# f103ret6_w25q64_20210714.net
KiCad netlist of a schematic drawn in Altium Designer
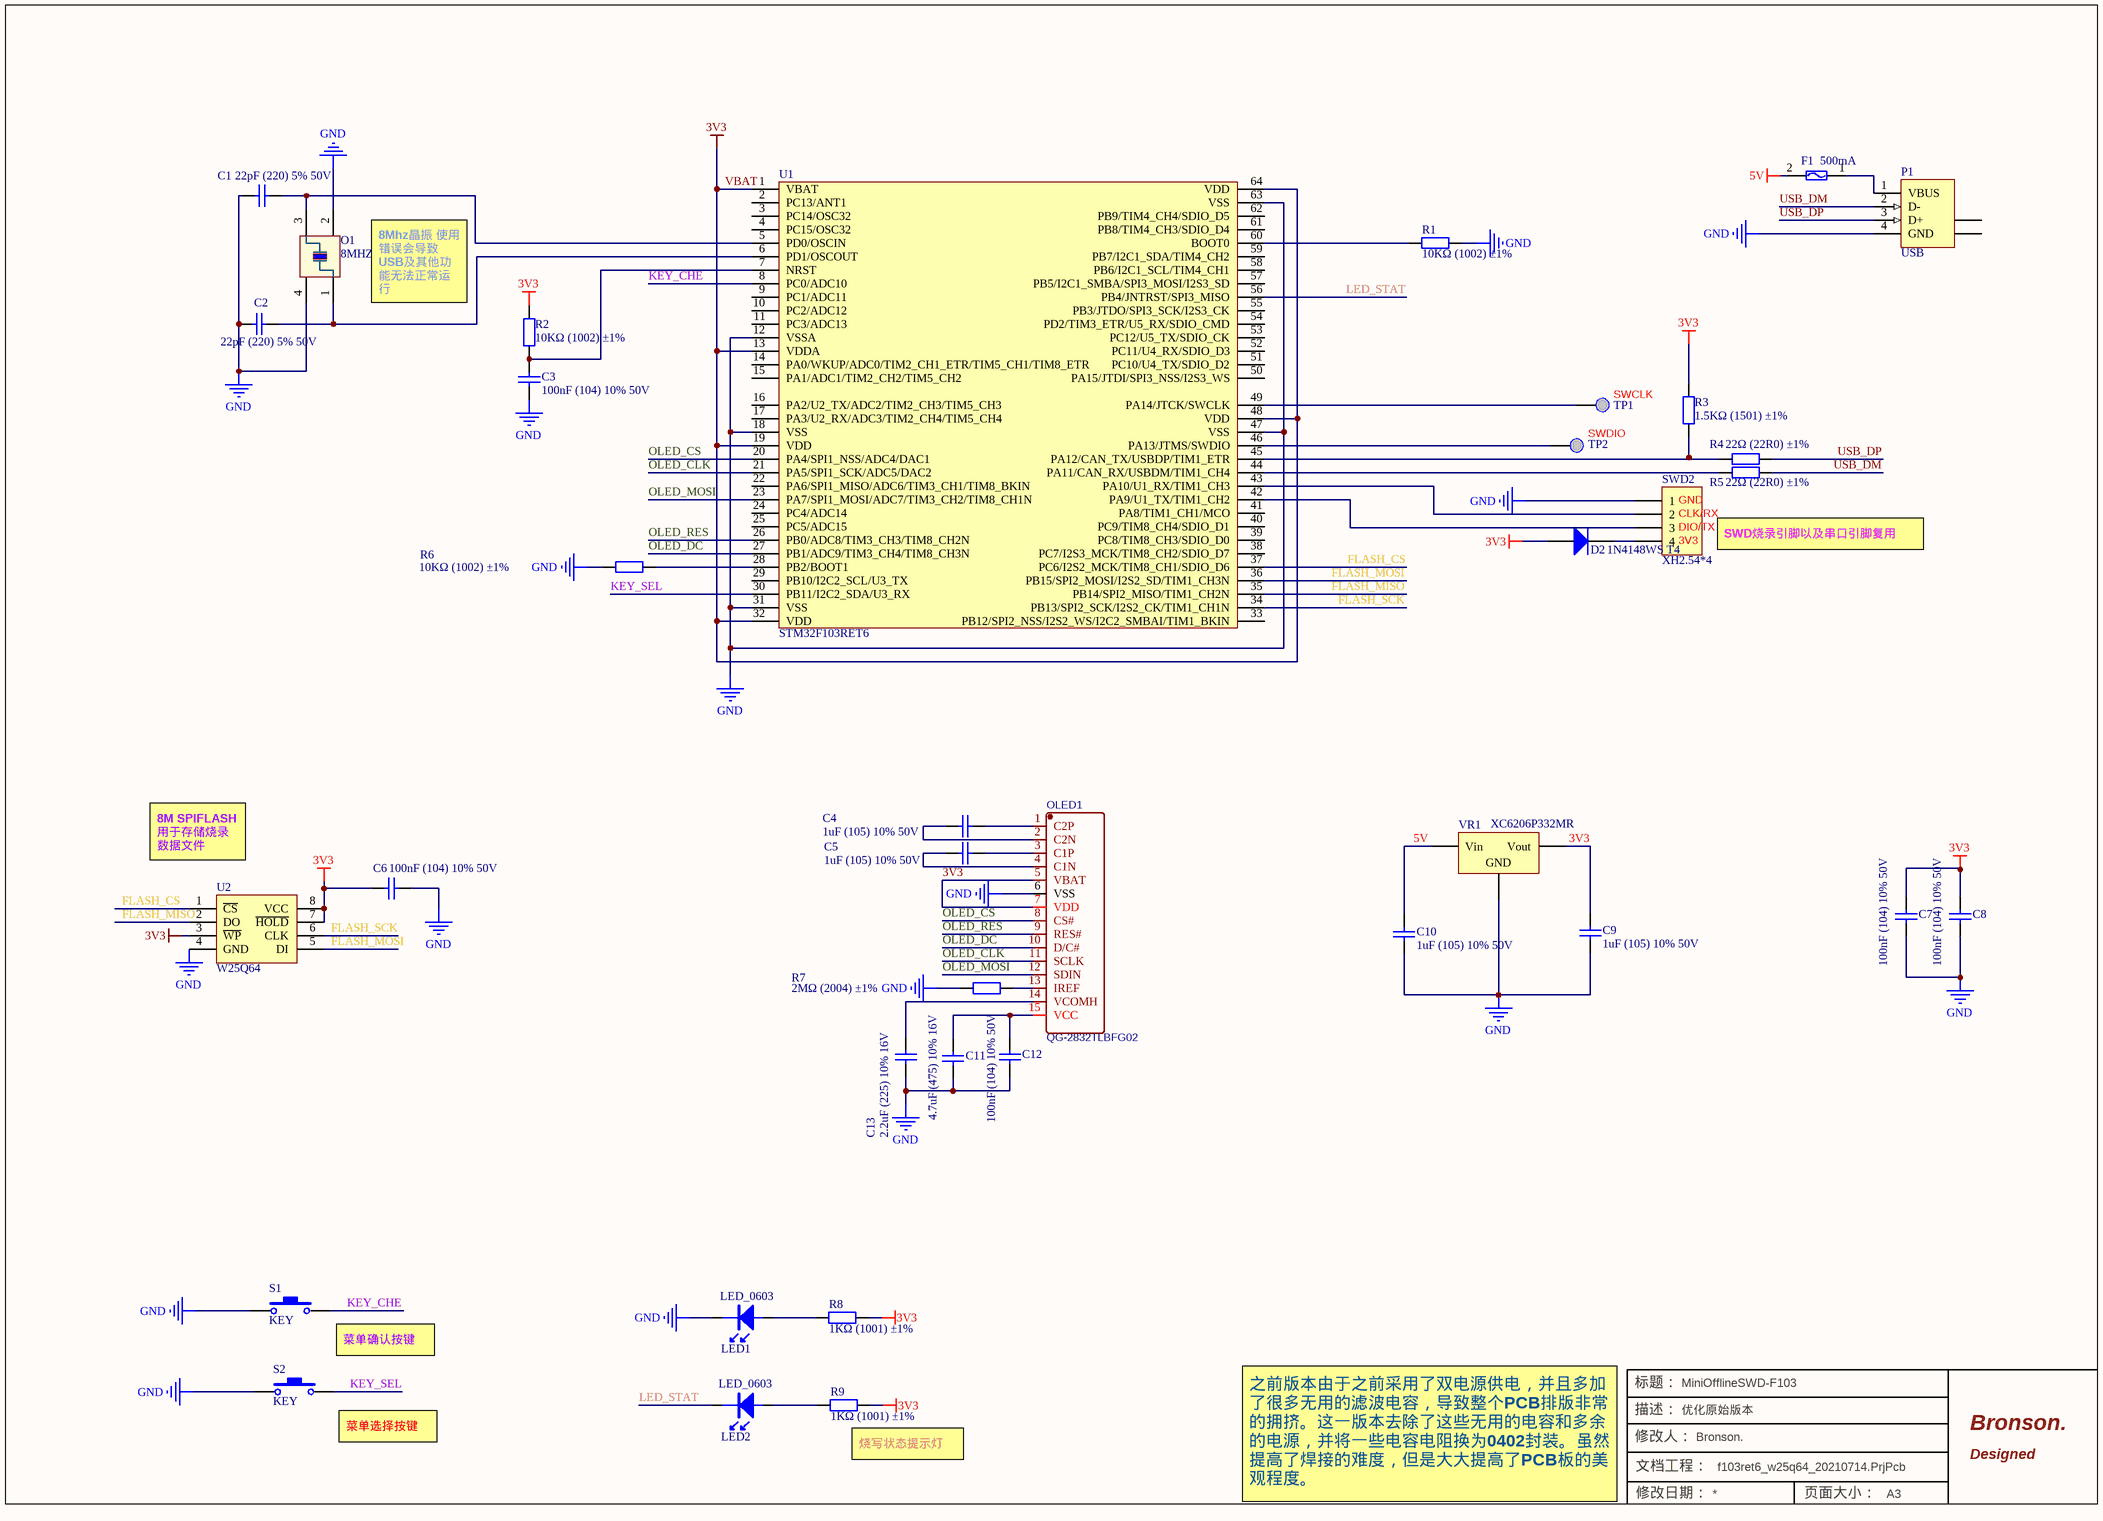
[diagram p0: f103ret6_w25q64_20210714.SchDoc]

(export (version "E")
  (design (tool "Eeschema 10.0.6"))
  (components
    (comp (ref "C1")
      (value "22pF (220) 5% 50V")
      (footprint "C0402")
      (description "贴片电容")
      (libsource (lib "Miscellaneous Devices LC") (part "0603 22pF (220) 5% 50V"))
    )
    (comp (ref "C2")
      (value "22pF (220) 5% 50V")
      (footprint "C0402")
      (description "贴片电容")
      (libsource (lib "Miscellaneous Devices LC") (part "0603 22pF (220) 5% 50V"))
    )
    (comp (ref "C3")
      (value "100nF (104) 10% 50V")
      (footprint "C0402")
      (description "贴片电容")
      (libsource (lib "Miscellaneous Devices LC") (part "0603 100nF (104) 10% 50V"))
    )
    (comp (ref "C4")
      (value "1uF (105) 10% 50V")
      (footprint "C0402")
      (description "贴片电容")
      (libsource (lib "Miscellaneous Devices LC") (part "0603 1uF (105) 10% 50V"))
    )
    (comp (ref "C5")
      (value "1uF (105) 10% 50V")
      (footprint "C0402")
      (description "贴片电容")
      (libsource (lib "Miscellaneous Devices LC") (part "0603 1uF (105) 10% 50V"))
    )
    (comp (ref "C6")
      (value "100nF (104) 10% 50V")
      (footprint "C0402")
      (description "贴片电容")
      (libsource (lib "Miscellaneous Devices LC") (part "0603 100nF (104) 10% 50V"))
    )
    (comp (ref "C7")
      (value "100nF (104) 10% 50V")
      (footprint "C0603")
      (description "贴片电容")
      (libsource (lib "Miscellaneous Devices LC") (part "0603 100nF (104) 10% 50V"))
    )
    (comp (ref "C8")
      (value "100nF (104) 10% 50V")
      (footprint "C0402")
      (description "贴片电容")
      (libsource (lib "Miscellaneous Devices LC") (part "0603 100nF (104) 10% 50V"))
    )
    (comp (ref "C9")
      (value "1uF (105) 10% 50V")
      (footprint "C0402")
      (description "贴片电容")
      (libsource (lib "Miscellaneous Devices LC") (part "0603 1uF (105) 10% 50V"))
    )
    (comp (ref "C10")
      (value "1uF (105) 10% 50V")
      (footprint "C0603")
      (description "贴片电容")
      (libsource (lib "Miscellaneous Devices LC") (part "0603 1uF (105) 10% 50V"))
    )
    (comp (ref "C11")
      (value "4.7uF (475) 10% 16V")
      (footprint "C0402")
      (description "贴片电容")
      (libsource (lib "Miscellaneous Devices LC") (part "0603 4.7uF (475) 10% 16V"))
    )
    (comp (ref "C12")
      (value "100nF (104) 10% 50V")
      (footprint "C0402")
      (description "贴片电容")
      (libsource (lib "Miscellaneous Devices LC") (part "0603 100nF (104) 10% 50V"))
    )
    (comp (ref "C13")
      (value "2.2uF (225) 10% 16V")
      (footprint "C0402")
      (description "贴片电容")
      (libsource (lib "Miscellaneous Devices LC") (part "0603 2.2uF (225) 10% 16V"))
    )
    (comp (ref "D2")
      (value "1N4148WS T4")
      (footprint "SOD-323")
      (description "二极管")
      (libsource (lib "Miscellaneous Devices LC") (part "SOD-323 1N4148WS T4"))
    )
    (comp (ref "F1")
      (value "500mA")
      (footprint "0603")
      (description "保险丝，熔断丝")
      (libsource (lib "Free Documents") (part "FUSE"))
    )
    (comp (ref "LED1")
      (value "LED_0603")
      (footprint "LED_0603_BLUE")
      (libsource (lib "28335lib") (part "LED"))
    )
    (comp (ref "LED2")
      (value "LED_0603")
      (footprint "LED_0603_RED")
      (libsource (lib "28335lib") (part "LED"))
    )
    (comp (ref "O1")
      (value "8MHZ")
      (footprint "3225")
      (description "OSC")
      (libsource (lib "altium-import") (part "root_1_OSC_"))
    )
    (comp (ref "OLED1")
      (value "QG-2832TLBFG02")
      (footprint "0.91-OLED")
      (fields (field (name "BOM_SUPPLIER PART") "C91220") (field (name "CONTRIBUTOR") "LCSC"))
      (libsource (lib "0.91-oled") (part "0.91-OLED"))
    )
    (comp (ref "P1")
      (value "USB")
      (footprint "USB_A/P_B")
      (description "USB 1.1, Right Angle, SMT, A Type, Plug, 4 Position, Natural")
      (fields (field (name "PUBLISHER") "Altium Limited"))
      (libsource (lib "AMP Serial Bus USB") (part "1470695-2"))
    )
    (comp (ref "R1")
      (value "10KΩ (1002) ±1%")
      (footprint "RES0402")
      (description "贴片电阻")
      (libsource (lib "Miscellaneous Devices LC") (part "0603 10KΩ (1002) 1%"))
    )
    (comp (ref "R2")
      (value "10KΩ (1002) ±1%")
      (footprint "RES0402")
      (description "贴片电阻")
      (libsource (lib "") (part "0603 10KΩ (1002) 1%_2"))
    )
    (comp (ref "R3")
      (value "1.5KΩ (1501) ±1%")
      (footprint "RES0402")
      (description "贴片电阻")
      (libsource (lib "Miscellaneous Devices LC") (part "0603 1.5KΩ (1501) 1%"))
    )
    (comp (ref "R4")
      (value "22Ω (22R0) ±1%")
      (footprint "RES0402")
      (description "贴片电阻")
      (libsource (lib "Miscellaneous Devices LC") (part "0603 22Ω (22R0) 1%"))
    )
    (comp (ref "R5")
      (value "22Ω (22R0) ±1%")
      (footprint "RES0402")
      (description "贴片电阻")
      (libsource (lib "Miscellaneous Devices LC") (part "0603 22Ω (22R0) 1%"))
    )
    (comp (ref "R6")
      (value "10KΩ (1002) ±1%")
      (footprint "RES0402")
      (description "贴片电阻")
      (libsource (lib "") (part "0603 10KΩ (1002) 1%_1"))
    )
    (comp (ref "R7")
      (value "2MΩ (2004) ±1%")
      (footprint "RES0603")
      (description "贴片电阻")
      (libsource (lib "Miscellaneous Devices LC") (part "0603 2MΩ (2004) 1%"))
    )
    (comp (ref "R8")
      (value "1KΩ (1001) ±1%")
      (footprint "RES0402")
      (description "贴片电阻")
      (libsource (lib "Miscellaneous Devices LC") (part "0603 1KΩ (1001) 1%"))
    )
    (comp (ref "R9")
      (value "1KΩ (1001) ±1%")
      (footprint "RES0402")
      (description "贴片电阻")
      (libsource (lib "Miscellaneous Devices LC") (part "0603 1KΩ (1001) 1%"))
    )
    (comp (ref "S1") (value "KEY") (footprint "KEY") (libsource (lib "altium-import") (part "root_0_KEY_")))
    (comp (ref "S2") (value "KEY") (footprint "KEY") (libsource (lib "altium-import") (part "root_0_KEY_")))
    (comp (ref "SWD2")
      (value "XH2.54*4")
      (footprint "XH2.54-WI-4P")
      (description "Header, 4-Pin")
      (fields (field (name "PUBLISHER") "Altium Limited"))
      (libsource (lib "Mogoo-GM_B1-PLCPCB-V1.0") (part "Header 4"))
    )
    (comp (ref "TP1") (value "IO") (footprint "TP") (libsource (lib "IMU_V1.1") (part "TP_SMD")))
    (comp (ref "TP2") (value "IO") (footprint "TP") (libsource (lib "IMU_V1.1") (part "TP_SMD")))
    (comp (ref "U1")
      (value "STM32F103RET6")
      (footprint "LQFP64")
      (description "STM32F103RxT6")
      (libsource (lib "Free Documents") (part "STM32F103RxT6"))
    )
    (comp (ref "U2")
      (value "W25Q64")
      (footprint "f103ret6_w25q64_20200910:SOP8_W")
      (description "W25Q")
      (libsource (lib "Free Documents") (part "W25Q"))
    )
    (comp (ref "VR1")
      (value "XC6206P332MR")
      (footprint "SOT-23-3L")
      (description "低压差线性稳压(LDO)")
      (libsource (lib "Miscellaneous Devices LC") (part "SOT-23 XC6206P332MR"))
    )
  )
  (nets
    (net (code "1") (name "/FLASH_CS") (class "Default")
      (node (ref "U1") (pin "37") (pinfunction "PC6/I2S2_MCK/TIM8_CH1/SDIO_D6_37") (pintype "passive"))
      (node (ref "U2") (pin "1") (pinfunction "~{CS}_1") (pintype "passive"))
    )
    (net (code "2") (name "/FLASH_MISO") (class "Default")
      (node (ref "U1") (pin "35") (pinfunction "PB14/SPI2_MISO/TIM1_CH2N_35") (pintype "passive"))
      (node (ref "U2") (pin "2") (pinfunction "DO_2") (pintype "passive"))
    )
    (net (code "3") (name "/FLASH_MOSI") (class "Default")
      (node (ref "U1") (pin "36") (pinfunction "PB15/SPI2_MOSI/I2S2_SD/TIM1_CH3N_36") (pintype "passive"))
      (node (ref "U2") (pin "5") (pinfunction "DI_5") (pintype "passive"))
    )
    (net (code "4") (name "/FLASH_SCK") (class "Default")
      (node (ref "U1") (pin "34") (pinfunction "PB13/SPI2_SCK/I2S2_CK/TIM1_CH1N_34") (pintype "passive"))
      (node (ref "U2") (pin "6") (pinfunction "CLK_6") (pintype "passive"))
    )
    (net (code "5") (name "/KEY_CHE") (class "Default")
      (node (ref "S1") (pin "2") (pinfunction "2_2") (pintype "power_in"))
      (node (ref "U1") (pin "8") (pinfunction "PC0/ADC10_8") (pintype "passive"))
    )
    (net (code "6") (name "/KEY_SEL") (class "Default")
      (node (ref "S2") (pin "2") (pinfunction "2_2") (pintype "power_in"))
      (node (ref "U1") (pin "30") (pinfunction "PB11/I2C2_SDA/U3_RX_30") (pintype "passive"))
    )
    (net (code "7") (name "/LED_STAT") (class "Default")
      (node (ref "LED2") (pin "2") (pinfunction "2_2") (pintype "passive"))
      (node (ref "U1") (pin "56") (pinfunction "PB4/JNTRST/SPI3_MISO_56") (pintype "passive"))
    )
    (net (code "8") (name "/OLED_CLK") (class "Default")
      (node (ref "OLED1") (pin "11") (pinfunction "SCLK_11") (pintype "passive"))
      (node (ref "U1") (pin "21") (pinfunction "PA5/SPI1_SCK/ADC5/DAC2_21") (pintype "passive"))
    )
    (net (code "9") (name "/OLED_CS") (class "Default")
      (node (ref "OLED1") (pin "8") (pinfunction "CS#_8") (pintype "passive"))
      (node (ref "U1") (pin "20") (pinfunction "PA4/SPI1_NSS/ADC4/DAC1_20") (pintype "passive"))
    )
    (net (code "10") (name "/OLED_DC") (class "Default")
      (node (ref "OLED1") (pin "10") (pinfunction "D/C#_10") (pintype "passive"))
      (node (ref "U1") (pin "27") (pinfunction "PB1/ADC9/TIM3_CH4/TIM8_CH3N_27") (pintype "passive"))
    )
    (net (code "11") (name "/OLED_MOSI") (class "Default")
      (node (ref "OLED1") (pin "12") (pinfunction "SDIN_12") (pintype "passive"))
      (node (ref "U1") (pin "23") (pinfunction "PA7/SPI1_MOSI/ADC7/TIM3_CH2/TIM8_CH1N_23") (pintype "passive"))
    )
    (net (code "12") (name "/OLED_RES") (class "Default")
      (node (ref "OLED1") (pin "9") (pinfunction "RES#_9") (pintype "passive"))
      (node (ref "U1") (pin "26") (pinfunction "PB0/ADC8/TIM3_CH3/TIM8_CH2N_26") (pintype "passive"))
    )
    (net (code "13") (name "/USB_DM") (class "Default")
      (node (ref "P1") (pin "2") (pinfunction "D-_2") (pintype "input"))
      (node (ref "R5") (pin "2") (pinfunction "2_2") (pintype "passive"))
    )
    (net (code "14") (name "/USB_DP") (class "Default")
      (node (ref "P1") (pin "3") (pinfunction "D+_3") (pintype "input"))
      (node (ref "R4") (pin "2") (pinfunction "2_2") (pintype "passive"))
    )
    (net (code "15") (name "3V3") (class "Default")
      (node (ref "C6") (pin "1") (pinfunction "1_1") (pintype "passive"))
      (node (ref "C7") (pin "2") (pinfunction "2_2") (pintype "passive"))
      (node (ref "C8") (pin "2") (pinfunction "2_2") (pintype "passive"))
      (node (ref "C9") (pin "2") (pinfunction "2_2") (pintype "passive"))
      (node (ref "D2") (pin "1") (pinfunction "A_1") (pintype "passive"))
      (node (ref "OLED1") (pin "5") (pinfunction "VBAT_5") (pintype "passive"))
      (node (ref "OLED1") (pin "7") (pinfunction "VDD_7") (pintype "passive"))
      (node (ref "R2") (pin "2") (pinfunction "2_2") (pintype "passive"))
      (node (ref "R3") (pin "1") (pinfunction "1_1") (pintype "passive"))
      (node (ref "R8") (pin "2") (pinfunction "2_2") (pintype "passive"))
      (node (ref "R9") (pin "2") (pinfunction "2_2") (pintype "passive"))
      (node (ref "U1") (pin "1") (pinfunction "VBAT_1") (pintype "passive"))
      (node (ref "U1") (pin "13") (pinfunction "VDDA_13") (pintype "passive"))
      (node (ref "U1") (pin "19") (pinfunction "VDD_19") (pintype "passive"))
      (node (ref "U1") (pin "32") (pinfunction "VDD_32") (pintype "passive"))
      (node (ref "U1") (pin "48") (pinfunction "VDD_48") (pintype "passive"))
      (node (ref "U1") (pin "64") (pinfunction "VDD_64") (pintype "passive"))
      (node (ref "U2") (pin "3") (pinfunction "~{WP}_3") (pintype "passive"))
      (node (ref "U2") (pin "7") (pinfunction "~{HOLD}_7") (pintype "passive"))
      (node (ref "U2") (pin "8") (pinfunction "VCC_8") (pintype "passive"))
      (node (ref "VR1") (pin "2") (pinfunction "Vout_2") (pintype "passive"))
    )
    (net (code "16") (name "5V") (class "Default")
      (node (ref "C10") (pin "2") (pinfunction "2_2") (pintype "passive"))
      (node (ref "F1") (pin "2") (pinfunction "5_2") (pintype "passive"))
      (node (ref "VR1") (pin "3") (pinfunction "Vin_3") (pintype "passive"))
    )
    (net (code "17") (name "GND") (class "Default")
      (node (ref "C1") (pin "2") (pinfunction "2_2") (pintype "passive"))
      (node (ref "C10") (pin "1") (pinfunction "1_1") (pintype "passive"))
      (node (ref "C11") (pin "1") (pinfunction "1_1") (pintype "passive"))
      (node (ref "C12") (pin "1") (pinfunction "1_1") (pintype "passive"))
      (node (ref "C13") (pin "1") (pinfunction "1_1") (pintype "passive"))
      (node (ref "C2") (pin "2") (pinfunction "2_2") (pintype "passive"))
      (node (ref "C3") (pin "1") (pinfunction "1_1") (pintype "passive"))
      (node (ref "C6") (pin "2") (pinfunction "2_2") (pintype "passive"))
      (node (ref "C7") (pin "1") (pinfunction "1_1") (pintype "passive"))
      (node (ref "C8") (pin "1") (pinfunction "1_1") (pintype "passive"))
      (node (ref "C9") (pin "1") (pinfunction "1_1") (pintype "passive"))
      (node (ref "LED1") (pin "2") (pinfunction "2_2") (pintype "passive"))
      (node (ref "O1") (pin "2") (pintype "passive"))
      (node (ref "O1") (pin "4") (pintype "passive"))
      (node (ref "OLED1") (pin "6") (pinfunction "VSS_6") (pintype "passive"))
      (node (ref "P1") (pin "4") (pinfunction "GND_4") (pintype "power_in"))
      (node (ref "R1") (pin "1") (pinfunction "1_1") (pintype "passive"))
      (node (ref "R6") (pin "1") (pinfunction "1_1") (pintype "passive"))
      (node (ref "R7") (pin "1") (pinfunction "1_1") (pintype "passive"))
      (node (ref "S1") (pin "1") (pinfunction "1_1") (pintype "power_in"))
      (node (ref "S2") (pin "1") (pinfunction "1_1") (pintype "power_in"))
      (node (ref "SWD2") (pin "1") (pinfunction "1_1") (pintype "passive"))
      (node (ref "U1") (pin "12") (pinfunction "VSSA_12") (pintype "passive"))
      (node (ref "U1") (pin "18") (pinfunction "VSS_18") (pintype "passive"))
      (node (ref "U1") (pin "31") (pinfunction "VSS_31") (pintype "passive"))
      (node (ref "U1") (pin "47") (pinfunction "VSS_47") (pintype "passive"))
      (node (ref "U1") (pin "63") (pinfunction "VSS_63") (pintype "passive"))
      (node (ref "U2") (pin "4") (pinfunction "GND_4") (pintype "passive"))
      (node (ref "VR1") (pin "1") (pinfunction "GND_1") (pintype "passive"))
    )
    (net (code "18") (name "Net-(D2-K)") (class "Default")
      (node (ref "D2") (pin "2") (pinfunction "K_2") (pintype "passive"))
      (node (ref "SWD2") (pin "4") (pinfunction "4_4") (pintype "passive"))
    )
    (net (code "19") (name "Net-(F1-4)") (class "Default")
      (node (ref "F1") (pin "1") (pinfunction "4_1") (pintype "passive"))
      (node (ref "P1") (pin "1") (pinfunction "VBUS_1") (pintype "power_in"))
    )
    (net (code "20") (name "Net-(LED1-Pad1)") (class "Default")
      (node (ref "LED1") (pin "1") (pinfunction "1_1") (pintype "passive"))
      (node (ref "R8") (pin "1") (pinfunction "1_1") (pintype "passive"))
    )
    (net (code "21") (name "Net-(LED2-Pad1)") (class "Default")
      (node (ref "LED2") (pin "1") (pinfunction "1_1") (pintype "passive"))
      (node (ref "R9") (pin "1") (pinfunction "1_1") (pintype "passive"))
    )
    (net (code "22") (name "Net-(OLED1-C1N)") (class "Default")
      (node (ref "C5") (pin "1") (pinfunction "1_1") (pintype "passive"))
      (node (ref "OLED1") (pin "4") (pinfunction "C1N_4") (pintype "passive"))
    )
    (net (code "23") (name "Net-(OLED1-C1P)") (class "Default")
      (node (ref "C5") (pin "2") (pinfunction "2_2") (pintype "passive"))
      (node (ref "OLED1") (pin "3") (pinfunction "C1P_3") (pintype "passive"))
    )
    (net (code "24") (name "Net-(OLED1-C2N)") (class "Default")
      (node (ref "C4") (pin "1") (pinfunction "1_1") (pintype "passive"))
      (node (ref "OLED1") (pin "2") (pinfunction "C2N_2") (pintype "passive"))
    )
    (net (code "25") (name "Net-(OLED1-C2P)") (class "Default")
      (node (ref "C4") (pin "2") (pinfunction "2_2") (pintype "passive"))
      (node (ref "OLED1") (pin "1") (pinfunction "C2P_1") (pintype "passive"))
    )
    (net (code "26") (name "Net-(OLED1-IREF)") (class "Default")
      (node (ref "OLED1") (pin "13") (pinfunction "IREF_13") (pintype "passive"))
      (node (ref "R7") (pin "2") (pinfunction "2_2") (pintype "passive"))
    )
    (net (code "27") (name "Net-(OLED1-VCC)") (class "Default")
      (node (ref "C11") (pin "2") (pinfunction "2_2") (pintype "passive"))
      (node (ref "C12") (pin "2") (pinfunction "2_2") (pintype "passive"))
      (node (ref "OLED1") (pin "15") (pinfunction "VCC_15") (pintype "passive"))
    )
    (net (code "28") (name "Net-(OLED1-VCOMH)") (class "Default")
      (node (ref "C13") (pin "2") (pinfunction "2_2") (pintype "passive"))
      (node (ref "OLED1") (pin "14") (pinfunction "VCOMH_14") (pintype "passive"))
    )
    (net (code "29") (name "Net-(U1-BOOT0)") (class "Default")
      (node (ref "R1") (pin "2") (pinfunction "2_2") (pintype "passive"))
      (node (ref "U1") (pin "60") (pinfunction "BOOT0_60") (pintype "passive"))
    )
    (net (code "30") (name "Net-(U1-NRST)") (class "Default")
      (node (ref "C3") (pin "2") (pinfunction "2_2") (pintype "passive"))
      (node (ref "R2") (pin "1") (pinfunction "1_1") (pintype "passive"))
      (node (ref "U1") (pin "7") (pinfunction "NRST_7") (pintype "passive"))
    )
    (net (code "31") (name "Net-(U1-PA9{slash}U1_TX{slash}TIM1_CH2)") (class "Default")
      (node (ref "SWD2") (pin "3") (pinfunction "3_3") (pintype "passive"))
      (node (ref "U1") (pin "42") (pinfunction "PA9/U1_TX/TIM1_CH2_42") (pintype "passive"))
    )
    (net (code "32") (name "Net-(U1-PA10{slash}U1_RX{slash}TIM1_CH3)") (class "Default")
      (node (ref "SWD2") (pin "2") (pinfunction "2_2") (pintype "passive"))
      (node (ref "U1") (pin "43") (pinfunction "PA10/U1_RX/TIM1_CH3_43") (pintype "passive"))
    )
    (net (code "33") (name "Net-(U1-PA11{slash}CAN_RX{slash}USBDM{slash}TIM1_CH4)") (class "Default")
      (node (ref "R5") (pin "1") (pinfunction "1_1") (pintype "passive"))
      (node (ref "U1") (pin "44") (pinfunction "PA11/CAN_RX/USBDM/TIM1_CH4_44") (pintype "passive"))
    )
    (net (code "34") (name "Net-(U1-PA12{slash}CAN_TX{slash}USBDP{slash}TIM1_ETR)") (class "Default")
      (node (ref "R3") (pin "2") (pinfunction "2_2") (pintype "passive"))
      (node (ref "R4") (pin "1") (pinfunction "1_1") (pintype "passive"))
      (node (ref "U1") (pin "45") (pinfunction "PA12/CAN_TX/USBDP/TIM1_ETR_45") (pintype "passive"))
    )
    (net (code "35") (name "Net-(U1-PA13{slash}JTMS{slash}SWDIO)") (class "Default")
      (node (ref "TP2") (pin "1") (pinfunction "1_1") (pintype "passive"))
      (node (ref "U1") (pin "46") (pinfunction "PA13/JTMS/SWDIO_46") (pintype "passive"))
    )
    (net (code "36") (name "Net-(U1-PA14{slash}JTCK{slash}SWCLK)") (class "Default")
      (node (ref "TP1") (pin "1") (pinfunction "1_1") (pintype "passive"))
      (node (ref "U1") (pin "49") (pinfunction "PA14/JTCK/SWCLK_49") (pintype "passive"))
    )
    (net (code "37") (name "Net-(U1-PB2{slash}BOOT1)") (class "Default")
      (node (ref "R6") (pin "2") (pinfunction "2_2") (pintype "passive"))
      (node (ref "U1") (pin "28") (pinfunction "PB2/BOOT1_28") (pintype "passive"))
    )
    (net (code "38") (name "Net-(U1-PD0{slash}OSCIN)") (class "Default")
      (node (ref "C1") (pin "1") (pinfunction "1_1") (pintype "passive"))
      (node (ref "O1") (pin "3") (pintype "passive"))
      (node (ref "U1") (pin "5") (pinfunction "PD0/OSCIN_5") (pintype "passive"))
    )
    (net (code "39") (name "Net-(U1-PD1{slash}OSCOUT)") (class "Default")
      (node (ref "C2") (pin "1") (pinfunction "1_1") (pintype "passive"))
      (node (ref "O1") (pin "1") (pintype "passive"))
      (node (ref "U1") (pin "6") (pinfunction "PD1/OSCOUT_6") (pintype "passive"))
    )
    (net (code "40") (name "unconnected-(P1-SHLD-Pad5)") (class "Default")
      (node (ref "P1") (pin "5") (pinfunction "SHLD_5") (pintype "passive"))
    )
    (net (code "41") (name "unconnected-(P1-SHLD-Pad6)") (class "Default")
      (node (ref "P1") (pin "6") (pinfunction "SHLD_6") (pintype "passive"))
    )
    (net (code "42") (name "unconnected-(U1-PA0{slash}WKUP{slash}ADC0{slash}TIM2_CH1_ETR{slash}TIM5_CH1{slash}TIM8_ETR-Pad14)") (class "Default")
      (node (ref "U1") (pin "14") (pinfunction "PA0/WKUP/ADC0/TIM2_CH1_ETR/TIM5_CH1/TIM8_ETR_14") (pintype "passive"))
    )
    (net (code "43") (name "unconnected-(U1-PA1{slash}ADC1{slash}TIM2_CH2{slash}TIM5_CH2-Pad15)") (class "Default")
      (node (ref "U1") (pin "15") (pinfunction "PA1/ADC1/TIM2_CH2/TIM5_CH2_15") (pintype "passive"))
    )
    (net (code "44") (name "unconnected-(U1-PA2{slash}U2_TX{slash}ADC2{slash}TIM2_CH3{slash}TIM5_CH3-Pad16)") (class "Default")
      (node (ref "U1") (pin "16") (pinfunction "PA2/U2_TX/ADC2/TIM2_CH3/TIM5_CH3_16") (pintype "passive"))
    )
    (net (code "45") (name "unconnected-(U1-PA3{slash}U2_RX{slash}ADC3{slash}TIM2_CH4{slash}TIM5_CH4-Pad17)") (class "Default")
      (node (ref "U1") (pin "17") (pinfunction "PA3/U2_RX/ADC3/TIM2_CH4/TIM5_CH4_17") (pintype "passive"))
    )
    (net (code "46") (name "unconnected-(U1-PA6{slash}SPI1_MISO{slash}ADC6{slash}TIM3_CH1{slash}TIM8_BKIN-Pad22)") (class "Default")
      (node (ref "U1") (pin "22") (pinfunction "PA6/SPI1_MISO/ADC6/TIM3_CH1/TIM8_BKIN_22") (pintype "passive"))
    )
    (net (code "47") (name "unconnected-(U1-PA8{slash}TIM1_CH1{slash}MCO-Pad41)") (class "Default")
      (node (ref "U1") (pin "41") (pinfunction "PA8/TIM1_CH1/MCO_41") (pintype "passive"))
    )
    (net (code "48") (name "unconnected-(U1-PA15{slash}JTDI{slash}SPI3_NSS{slash}I2S3_WS-Pad50)") (class "Default")
      (node (ref "U1") (pin "50") (pinfunction "PA15/JTDI/SPI3_NSS/I2S3_WS_50") (pintype "passive"))
    )
    (net (code "49") (name "unconnected-(U1-PB3{slash}JTDO{slash}SPI3_SCK{slash}I2S3_CK-Pad55)") (class "Default")
      (node (ref "U1") (pin "55") (pinfunction "PB3/JTDO/SPI3_SCK/I2S3_CK_55") (pintype "passive"))
    )
    (net (code "50") (name "unconnected-(U1-PB5{slash}I2C1_SMBA{slash}SPI3_MOSI{slash}I2S3_SD-Pad57)") (class "Default")
      (node (ref "U1") (pin "57") (pinfunction "PB5/I2C1_SMBA/SPI3_MOSI/I2S3_SD_57") (pintype "passive"))
    )
    (net (code "51") (name "unconnected-(U1-PB6{slash}I2C1_SCL{slash}TIM4_CH1-Pad58)") (class "Default")
      (node (ref "U1") (pin "58") (pinfunction "PB6/I2C1_SCL/TIM4_CH1_58") (pintype "passive"))
    )
    (net (code "52") (name "unconnected-(U1-PB7{slash}I2C1_SDA{slash}TIM4_CH2-Pad59)") (class "Default")
      (node (ref "U1") (pin "59") (pinfunction "PB7/I2C1_SDA/TIM4_CH2_59") (pintype "passive"))
    )
    (net (code "53") (name "unconnected-(U1-PB8{slash}TIM4_CH3{slash}SDIO_D4-Pad61)") (class "Default")
      (node (ref "U1") (pin "61") (pinfunction "PB8/TIM4_CH3/SDIO_D4_61") (pintype "passive"))
    )
    (net (code "54") (name "unconnected-(U1-PB9{slash}TIM4_CH4{slash}SDIO_D5-Pad62)") (class "Default")
      (node (ref "U1") (pin "62") (pinfunction "PB9/TIM4_CH4/SDIO_D5_62") (pintype "passive"))
    )
    (net (code "55") (name "unconnected-(U1-PB10{slash}I2C2_SCL{slash}U3_TX-Pad29)") (class "Default")
      (node (ref "U1") (pin "29") (pinfunction "PB10/I2C2_SCL/U3_TX_29") (pintype "passive"))
    )
    (net (code "56") (name "unconnected-(U1-PB12{slash}SPI2_NSS{slash}I2S2_WS{slash}I2C2_SMBAI{slash}TIM1_BKIN-Pad33)") (class "Default")
      (node (ref "U1") (pin "33") (pinfunction "PB12/SPI2_NSS/I2S2_WS/I2C2_SMBAI/TIM1_BKIN_33") (pintype "passive"))
    )
    (net (code "57") (name "unconnected-(U1-PC1{slash}ADC11-Pad9)") (class "Default")
      (node (ref "U1") (pin "9") (pinfunction "PC1/ADC11_9") (pintype "passive"))
    )
    (net (code "58") (name "unconnected-(U1-PC2{slash}ADC12-Pad10)") (class "Default")
      (node (ref "U1") (pin "10") (pinfunction "PC2/ADC12_10") (pintype "passive"))
    )
    (net (code "59") (name "unconnected-(U1-PC3{slash}ADC13-Pad11)") (class "Default")
      (node (ref "U1") (pin "11") (pinfunction "PC3/ADC13_11") (pintype "passive"))
    )
    (net (code "60") (name "unconnected-(U1-PC4{slash}ADC14-Pad24)") (class "Default")
      (node (ref "U1") (pin "24") (pinfunction "PC4/ADC14_24") (pintype "passive"))
    )
    (net (code "61") (name "unconnected-(U1-PC5{slash}ADC15-Pad25)") (class "Default")
      (node (ref "U1") (pin "25") (pinfunction "PC5/ADC15_25") (pintype "passive"))
    )
    (net (code "62") (name "unconnected-(U1-PC7{slash}I2S3_MCK{slash}TIM8_CH2{slash}SDIO_D7-Pad38)") (class "Default")
      (node (ref "U1") (pin "38") (pinfunction "PC7/I2S3_MCK/TIM8_CH2/SDIO_D7_38") (pintype "passive"))
    )
    (net (code "63") (name "unconnected-(U1-PC8{slash}TIM8_CH3{slash}SDIO_D0-Pad39)") (class "Default")
      (node (ref "U1") (pin "39") (pinfunction "PC8/TIM8_CH3/SDIO_D0_39") (pintype "passive"))
    )
    (net (code "64") (name "unconnected-(U1-PC9{slash}TIM8_CH4{slash}SDIO_D1-Pad40)") (class "Default")
      (node (ref "U1") (pin "40") (pinfunction "PC9/TIM8_CH4/SDIO_D1_40") (pintype "passive"))
    )
    (net (code "65") (name "unconnected-(U1-PC10{slash}U4_TX{slash}SDIO_D2-Pad51)") (class "Default")
      (node (ref "U1") (pin "51") (pinfunction "PC10/U4_TX/SDIO_D2_51") (pintype "passive"))
    )
    (net (code "66") (name "unconnected-(U1-PC11{slash}U4_RX{slash}SDIO_D3-Pad52)") (class "Default")
      (node (ref "U1") (pin "52") (pinfunction "PC11/U4_RX/SDIO_D3_52") (pintype "passive"))
    )
    (net (code "67") (name "unconnected-(U1-PC12{slash}U5_TX{slash}SDIO_CK-Pad53)") (class "Default")
      (node (ref "U1") (pin "53") (pinfunction "PC12/U5_TX/SDIO_CK_53") (pintype "passive"))
    )
    (net (code "68") (name "unconnected-(U1-PC13{slash}ANT1-Pad2)") (class "Default")
      (node (ref "U1") (pin "2") (pinfunction "PC13/ANT1_2") (pintype "passive"))
    )
    (net (code "69") (name "unconnected-(U1-PC14{slash}OSC32-Pad3)") (class "Default")
      (node (ref "U1") (pin "3") (pinfunction "PC14/OSC32_3") (pintype "passive"))
    )
    (net (code "70") (name "unconnected-(U1-PC15{slash}OSC32-Pad4)") (class "Default")
      (node (ref "U1") (pin "4") (pinfunction "PC15/OSC32_4") (pintype "passive"))
    )
    (net (code "71") (name "unconnected-(U1-PD2{slash}TIM3_ETR{slash}U5_RX{slash}SDIO_CMD-Pad54)") (class "Default")
      (node (ref "U1") (pin "54") (pinfunction "PD2/TIM3_ETR/U5_RX/SDIO_CMD_54") (pintype "passive"))
    )
  )
)
